# PiBoard1_1.net
KiCad netlist of a schematic drawn in EAGLE
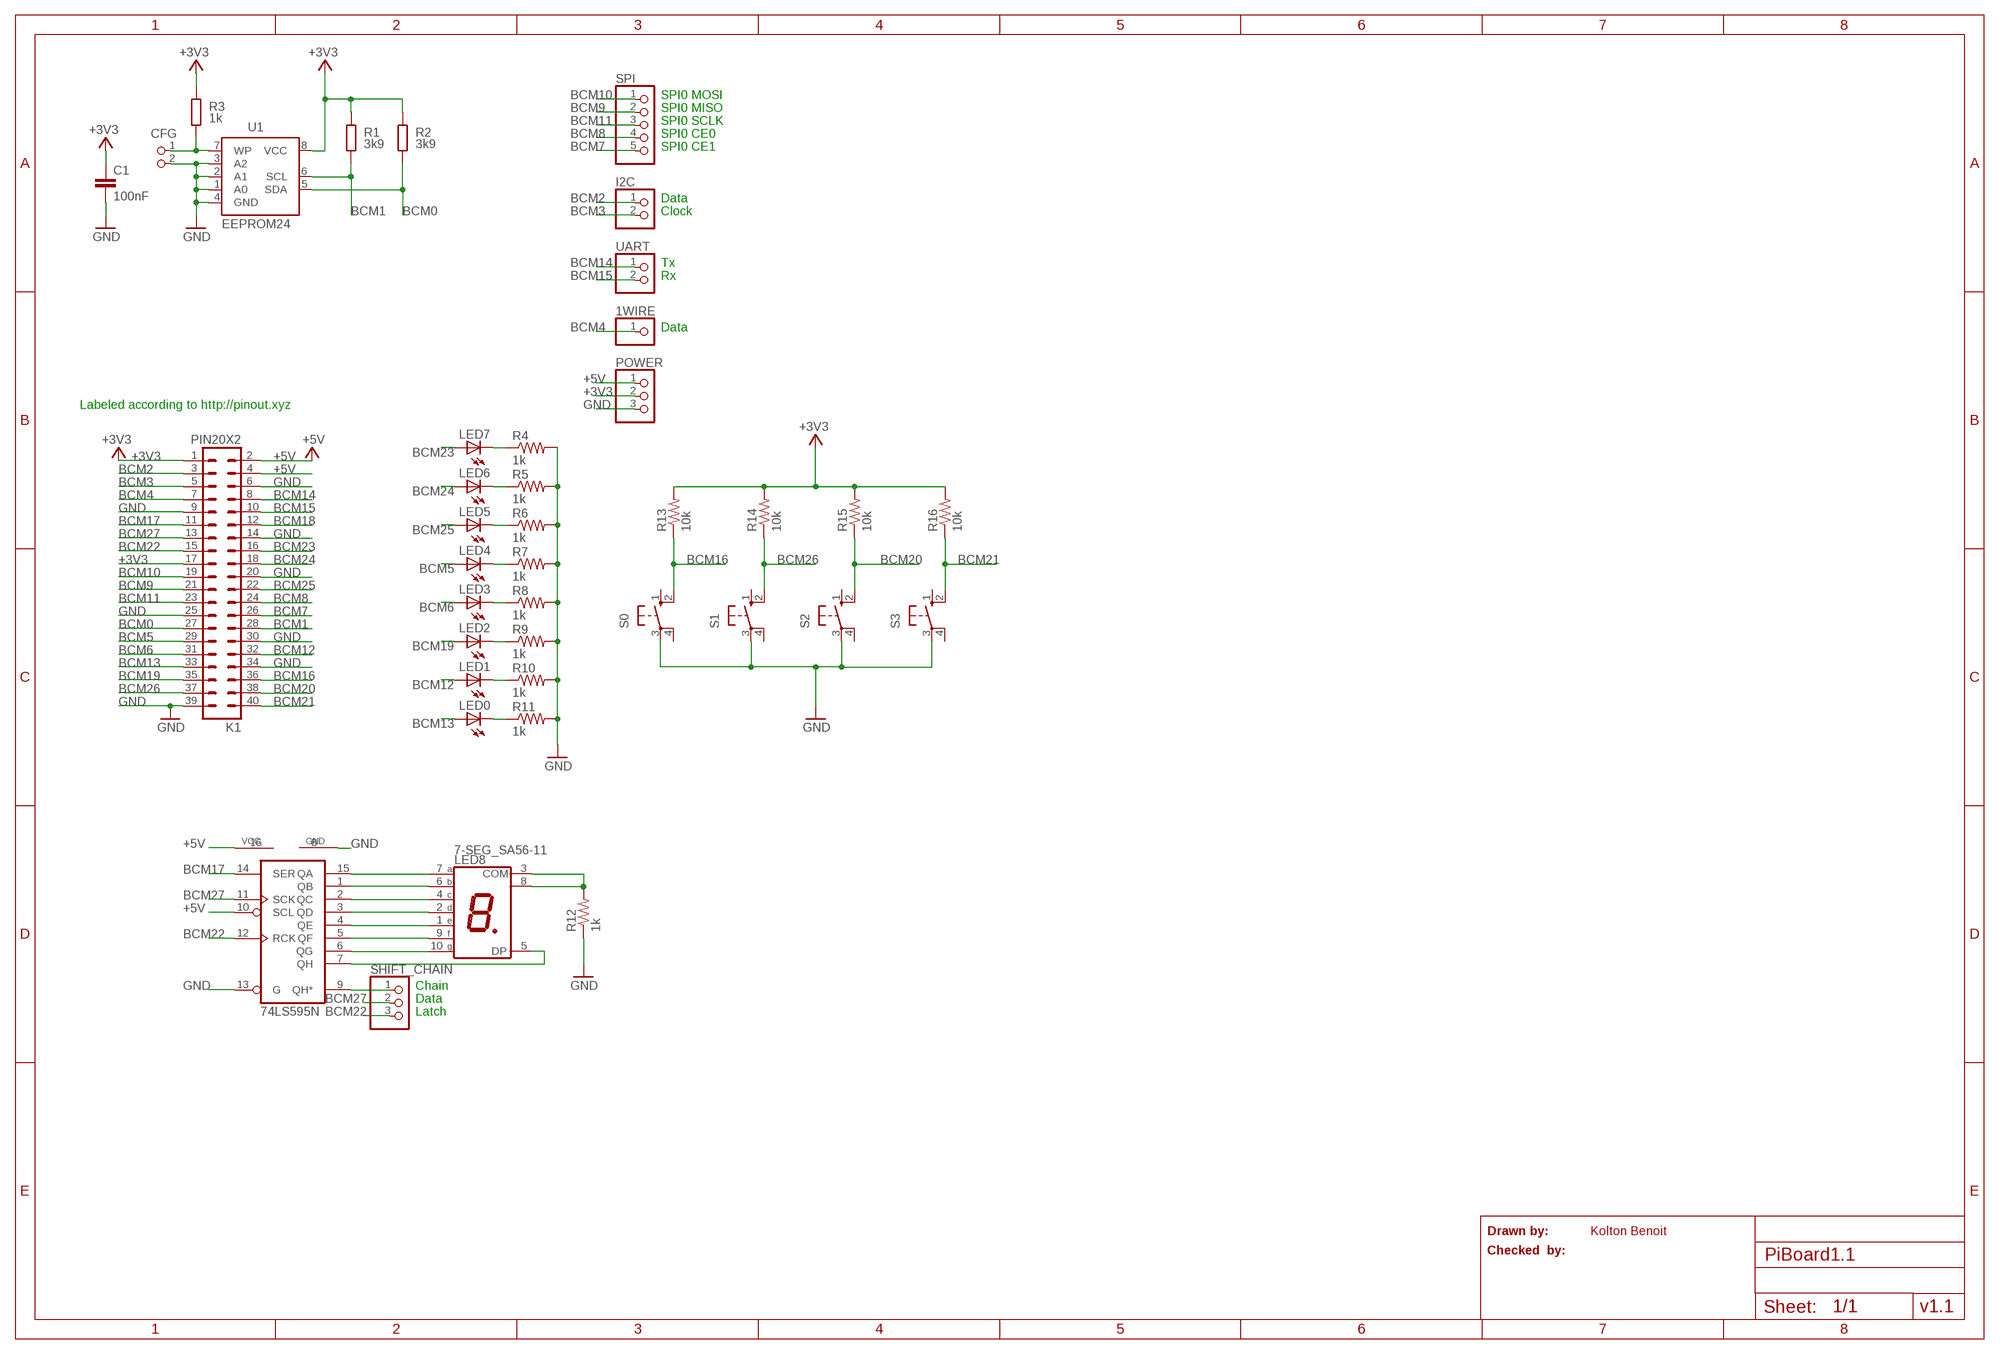
[diagram p0: schematic, sheet 1]

(export (version "E")
  (design (tool "Eeschema 10.0.6"))
  (components
    (comp (ref "1WIRE")
      (value "PINHD-1X1")
      (footprint "eagle-import:1X01")
      (libsource (lib "eagle-import") (part "PINHD-1X1"))
    )
    (comp (ref "C1")
      (value "100nF")
      (footprint "eagle-import:C0805K")
      (libsource (lib "eagle-import") (part "C-EUC0805K"))
    )
    (comp (ref "CFG")
      (value "PIN2_100")
      (footprint "eagle-import:PIN_W_2")
      (libsource (lib "eagle-import") (part "PIN2_100"))
    )
    (comp (ref "I2C")
      (value "PINHD-1X2")
      (footprint "eagle-import:1X02")
      (libsource (lib "eagle-import") (part "PINHD-1X2"))
    )
    (comp (ref "K1")
      (value "PIN20X2")
      (footprint "eagle-import:PIN_20X2")
      (libsource (lib "eagle-import") (part "PIN20X2"))
    )
    (comp (ref "LED0")
      (value "LED3MM")
      (footprint "eagle-import:LED3MM")
      (libsource (lib "eagle-import") (part "LED3MM"))
    )
    (comp (ref "LED1")
      (value "LED3MM")
      (footprint "eagle-import:LED3MM")
      (libsource (lib "eagle-import") (part "LED3MM"))
    )
    (comp (ref "LED2")
      (value "LED3MM")
      (footprint "eagle-import:LED3MM")
      (libsource (lib "eagle-import") (part "LED3MM"))
    )
    (comp (ref "LED3")
      (value "LED3MM")
      (footprint "eagle-import:LED3MM")
      (libsource (lib "eagle-import") (part "LED3MM"))
    )
    (comp (ref "LED4")
      (value "LED3MM")
      (footprint "eagle-import:LED3MM")
      (libsource (lib "eagle-import") (part "LED3MM"))
    )
    (comp (ref "LED5")
      (value "LED3MM")
      (footprint "eagle-import:LED3MM")
      (libsource (lib "eagle-import") (part "LED3MM"))
    )
    (comp (ref "LED6")
      (value "LED3MM")
      (footprint "eagle-import:LED3MM")
      (libsource (lib "eagle-import") (part "LED3MM"))
    )
    (comp (ref "LED7")
      (value "LED3MM")
      (footprint "eagle-import:LED3MM")
      (libsource (lib "eagle-import") (part "LED3MM"))
    )
    (comp (ref "LED8")
      (value "7-SEG_SA56-11")
      (footprint "eagle-import:SA56-11")
      (libsource (lib "eagle-import") (part "7-SEG_SA56-11"))
    )
    (comp (ref "POWER")
      (value "PINHD-1X3")
      (footprint "eagle-import:1X03")
      (libsource (lib "eagle-import") (part "PINHD-1X3"))
    )
    (comp (ref "R1")
      (value "3k9")
      (footprint "eagle-import:M0805@1")
      (fields (field (name "TOLERANCE") "5%"))
      (libsource (lib "eagle-import") (part "R-EU_M0805"))
    )
    (comp (ref "R2")
      (value "3k9")
      (footprint "eagle-import:M0805@1")
      (fields (field (name "TOLERANCE") "5%"))
      (libsource (lib "eagle-import") (part "R-EU_M0805"))
    )
    (comp (ref "R3")
      (value "1k")
      (footprint "eagle-import:M0805@1")
      (fields (field (name "TOLERANCE") "5%"))
      (libsource (lib "eagle-import") (part "R-EU_M0805"))
    )
    (comp (ref "R4")
      (value "1k")
      (footprint "eagle-import:0204_7")
      (libsource (lib "eagle-import") (part "R-US_0204/7"))
    )
    (comp (ref "R5")
      (value "1k")
      (footprint "eagle-import:0204_7")
      (libsource (lib "eagle-import") (part "R-US_0204/7"))
    )
    (comp (ref "R6")
      (value "1k")
      (footprint "eagle-import:0204_7")
      (libsource (lib "eagle-import") (part "R-US_0204/7"))
    )
    (comp (ref "R7")
      (value "1k")
      (footprint "eagle-import:0204_7")
      (libsource (lib "eagle-import") (part "R-US_0204/7"))
    )
    (comp (ref "R8")
      (value "1k")
      (footprint "eagle-import:0204_7")
      (libsource (lib "eagle-import") (part "R-US_0204/7"))
    )
    (comp (ref "R9")
      (value "1k")
      (footprint "eagle-import:0204_7")
      (libsource (lib "eagle-import") (part "R-US_0204/7"))
    )
    (comp (ref "R10")
      (value "1k")
      (footprint "eagle-import:0204_7")
      (libsource (lib "eagle-import") (part "R-US_0204/7"))
    )
    (comp (ref "R11")
      (value "1k")
      (footprint "eagle-import:0204_7")
      (libsource (lib "eagle-import") (part "R-US_0204/7"))
    )
    (comp (ref "R12")
      (value "1k")
      (footprint "eagle-import:0204_7")
      (libsource (lib "eagle-import") (part "R-US_0204/7"))
    )
    (comp (ref "R13")
      (value "10k")
      (footprint "eagle-import:0204_7")
      (libsource (lib "eagle-import") (part "R-US_0204/7"))
    )
    (comp (ref "R14")
      (value "10k")
      (footprint "eagle-import:0204_7")
      (libsource (lib "eagle-import") (part "R-US_0204/7"))
    )
    (comp (ref "R15")
      (value "10k")
      (footprint "eagle-import:0204_7")
      (libsource (lib "eagle-import") (part "R-US_0204/7"))
    )
    (comp (ref "R16")
      (value "10k")
      (footprint "eagle-import:0204_7")
      (libsource (lib "eagle-import") (part "R-US_0204/7"))
    )
    (comp (ref "S0")
      (value "10-XX")
      (footprint "eagle-import:B3F-10XX")
      (fields (field (name "MPN") "B3F-1000"))
      (libsource (lib "eagle-import") (part "10-XX"))
    )
    (comp (ref "S1")
      (value "10-XX")
      (footprint "eagle-import:B3F-10XX")
      (fields (field (name "MPN") "B3F-1000"))
      (libsource (lib "eagle-import") (part "10-XX"))
    )
    (comp (ref "S2")
      (value "10-XX")
      (footprint "eagle-import:B3F-10XX")
      (fields (field (name "MPN") "B3F-1000"))
      (libsource (lib "eagle-import") (part "10-XX"))
    )
    (comp (ref "S3")
      (value "10-XX")
      (footprint "eagle-import:B3F-10XX")
      (fields (field (name "MPN") "B3F-1000"))
      (libsource (lib "eagle-import") (part "10-XX"))
    )
    (comp (ref "SHIFT")
      (value "74LS595N")
      (footprint "eagle-import:DIL16")
      (libsource (lib "eagle-import") (part "74595NLS"))
    )
    (comp (ref "SHIFT_CHAIN")
      (value "PINHD-1X3")
      (footprint "eagle-import:1X03")
      (libsource (lib "eagle-import") (part "PINHD-1X3"))
    )
    (comp (ref "SPI")
      (value "PINHD-1X5")
      (footprint "eagle-import:1X05")
      (libsource (lib "eagle-import") (part "PINHD-1X5"))
    )
    (comp (ref "U1")
      (value "EEPROM24")
      (footprint "eagle-import:SOIC8")
      (libsource (lib "eagle-import") (part "EEPROM24"))
    )
    (comp (ref "UART")
      (value "PINHD-1X2")
      (footprint "eagle-import:1X02")
      (libsource (lib "eagle-import") (part "PINHD-1X2"))
    )
  )
  (nets
    (net (code "1") (name "+3V3") (class "Default")
      (node (ref "C1") (pin "1") (pinfunction "1_1") (pintype "passive"))
      (node (ref "K1") (pin "1") (pinfunction "1_1") (pintype "passive"))
      (node (ref "K1") (pin "17") (pinfunction "17_17") (pintype "passive"))
      (node (ref "POWER") (pin "2") (pinfunction "2_2") (pintype "passive"))
      (node (ref "R1") (pin "2") (pinfunction "2_2") (pintype "passive"))
      (node (ref "R13") (pin "2") (pinfunction "2_2") (pintype "passive"))
      (node (ref "R14") (pin "2") (pinfunction "2_2") (pintype "passive"))
      (node (ref "R15") (pin "2") (pinfunction "2_2") (pintype "passive"))
      (node (ref "R16") (pin "2") (pinfunction "2_2") (pintype "passive"))
      (node (ref "R2") (pin "2") (pinfunction "2_2") (pintype "passive"))
      (node (ref "R3") (pin "2") (pinfunction "2_2") (pintype "passive"))
      (node (ref "U1") (pin "8") (pinfunction "VCC_8") (pintype "power_in"))
    )
    (net (code "2") (name "+5V") (class "Default")
      (node (ref "K1") (pin "2") (pinfunction "2_2") (pintype "passive"))
      (node (ref "K1") (pin "4") (pinfunction "4_4") (pintype "passive"))
      (node (ref "POWER") (pin "1") (pinfunction "1_1") (pintype "passive"))
      (node (ref "SHIFT") (pin "10") (pinfunction "SCL_10") (pintype "input"))
      (node (ref "SHIFT") (pin "16") (pinfunction "VCC_16") (pintype "power_in"))
    )
    (net (code "3") (name "/BCM0") (class "Default")
      (node (ref "K1") (pin "27") (pinfunction "27_27") (pintype "passive"))
      (node (ref "R2") (pin "1") (pinfunction "1_1") (pintype "passive"))
      (node (ref "U1") (pin "5") (pinfunction "SDA_5") (pintype "bidirectional"))
    )
    (net (code "4") (name "/BCM1") (class "Default")
      (node (ref "K1") (pin "28") (pinfunction "28_28") (pintype "passive"))
      (node (ref "R1") (pin "1") (pinfunction "1_1") (pintype "passive"))
      (node (ref "U1") (pin "6") (pinfunction "SCL_6") (pintype "input"))
    )
    (net (code "5") (name "/BCM2") (class "Default")
      (node (ref "I2C") (pin "1") (pinfunction "1_1") (pintype "passive"))
      (node (ref "K1") (pin "3") (pinfunction "3_3") (pintype "passive"))
    )
    (net (code "6") (name "/BCM3") (class "Default")
      (node (ref "I2C") (pin "2") (pinfunction "2_2") (pintype "passive"))
      (node (ref "K1") (pin "5") (pinfunction "5_5") (pintype "passive"))
    )
    (net (code "7") (name "/BCM4") (class "Default")
      (node (ref "1WIRE") (pin "1") (pinfunction "1_1") (pintype "passive"))
      (node (ref "K1") (pin "7") (pinfunction "7_7") (pintype "passive"))
    )
    (net (code "8") (name "/BCM5") (class "Default")
      (node (ref "K1") (pin "29") (pinfunction "29_29") (pintype "passive"))
      (node (ref "LED4") (pin "A") (pinfunction "A_A") (pintype "passive"))
    )
    (net (code "9") (name "/BCM6") (class "Default")
      (node (ref "K1") (pin "31") (pinfunction "31_31") (pintype "passive"))
      (node (ref "LED3") (pin "A") (pinfunction "A_A") (pintype "passive"))
    )
    (net (code "10") (name "/BCM7") (class "Default")
      (node (ref "K1") (pin "26") (pinfunction "26_26") (pintype "passive"))
      (node (ref "SPI") (pin "5") (pinfunction "5_5") (pintype "passive"))
    )
    (net (code "11") (name "/BCM8") (class "Default")
      (node (ref "K1") (pin "24") (pinfunction "24_24") (pintype "passive"))
      (node (ref "SPI") (pin "4") (pinfunction "4_4") (pintype "passive"))
    )
    (net (code "12") (name "/BCM9") (class "Default")
      (node (ref "K1") (pin "21") (pinfunction "21_21") (pintype "passive"))
      (node (ref "SPI") (pin "2") (pinfunction "2_2") (pintype "passive"))
    )
    (net (code "13") (name "/BCM10") (class "Default")
      (node (ref "K1") (pin "19") (pinfunction "19_19") (pintype "passive"))
      (node (ref "SPI") (pin "1") (pinfunction "1_1") (pintype "passive"))
    )
    (net (code "14") (name "/BCM11") (class "Default")
      (node (ref "K1") (pin "23") (pinfunction "23_23") (pintype "passive"))
      (node (ref "SPI") (pin "3") (pinfunction "3_3") (pintype "passive"))
    )
    (net (code "15") (name "/BCM12") (class "Default")
      (node (ref "K1") (pin "32") (pinfunction "32_32") (pintype "passive"))
      (node (ref "LED1") (pin "A") (pinfunction "A_A") (pintype "passive"))
    )
    (net (code "16") (name "/BCM13") (class "Default")
      (node (ref "K1") (pin "33") (pinfunction "33_33") (pintype "passive"))
      (node (ref "LED0") (pin "A") (pinfunction "A_A") (pintype "passive"))
    )
    (net (code "17") (name "/BCM14") (class "Default")
      (node (ref "K1") (pin "8") (pinfunction "8_8") (pintype "passive"))
      (node (ref "UART") (pin "1") (pinfunction "1_1") (pintype "passive"))
    )
    (net (code "18") (name "/BCM15") (class "Default")
      (node (ref "K1") (pin "10") (pinfunction "10_10") (pintype "passive"))
      (node (ref "UART") (pin "2") (pinfunction "2_2") (pintype "passive"))
    )
    (net (code "19") (name "/BCM16") (class "Default")
      (node (ref "K1") (pin "36") (pinfunction "36_36") (pintype "passive"))
      (node (ref "R13") (pin "1") (pinfunction "1_1") (pintype "passive"))
      (node (ref "S0") (pin "2") (pinfunction "S1_2") (pintype "passive"))
    )
    (net (code "20") (name "/BCM17") (class "Default")
      (node (ref "K1") (pin "11") (pinfunction "11_11") (pintype "passive"))
      (node (ref "SHIFT") (pin "14") (pinfunction "SER_14") (pintype "input"))
    )
    (net (code "21") (name "/BCM18") (class "Default")
      (node (ref "K1") (pin "12") (pinfunction "12_12") (pintype "passive"))
    )
    (net (code "22") (name "/BCM19") (class "Default")
      (node (ref "K1") (pin "35") (pinfunction "35_35") (pintype "passive"))
      (node (ref "LED2") (pin "A") (pinfunction "A_A") (pintype "passive"))
    )
    (net (code "23") (name "/BCM20") (class "Default")
      (node (ref "K1") (pin "38") (pinfunction "38_38") (pintype "passive"))
      (node (ref "R15") (pin "1") (pinfunction "1_1") (pintype "passive"))
      (node (ref "S2") (pin "2") (pinfunction "S1_2") (pintype "passive"))
    )
    (net (code "24") (name "/BCM21") (class "Default")
      (node (ref "K1") (pin "40") (pinfunction "40_40") (pintype "passive"))
      (node (ref "R16") (pin "1") (pinfunction "1_1") (pintype "passive"))
      (node (ref "S3") (pin "2") (pinfunction "S1_2") (pintype "passive"))
    )
    (net (code "25") (name "/BCM22") (class "Default")
      (node (ref "K1") (pin "15") (pinfunction "15_15") (pintype "passive"))
      (node (ref "SHIFT") (pin "12") (pinfunction "RCK_12") (pintype "input"))
      (node (ref "SHIFT_CHAIN") (pin "3") (pinfunction "3_3") (pintype "passive"))
    )
    (net (code "26") (name "/BCM23") (class "Default")
      (node (ref "K1") (pin "16") (pinfunction "16_16") (pintype "passive"))
      (node (ref "LED7") (pin "A") (pinfunction "A_A") (pintype "passive"))
    )
    (net (code "27") (name "/BCM24") (class "Default")
      (node (ref "K1") (pin "18") (pinfunction "18_18") (pintype "passive"))
      (node (ref "LED6") (pin "A") (pinfunction "A_A") (pintype "passive"))
    )
    (net (code "28") (name "/BCM25") (class "Default")
      (node (ref "K1") (pin "22") (pinfunction "22_22") (pintype "passive"))
      (node (ref "LED5") (pin "A") (pinfunction "A_A") (pintype "passive"))
    )
    (net (code "29") (name "/BCM26") (class "Default")
      (node (ref "K1") (pin "37") (pinfunction "37_37") (pintype "passive"))
      (node (ref "R14") (pin "1") (pinfunction "1_1") (pintype "passive"))
      (node (ref "S1") (pin "2") (pinfunction "S1_2") (pintype "passive"))
    )
    (net (code "30") (name "/BCM27") (class "Default")
      (node (ref "K1") (pin "13") (pinfunction "13_13") (pintype "passive"))
      (node (ref "SHIFT") (pin "11") (pinfunction "SCK_11") (pintype "input"))
      (node (ref "SHIFT_CHAIN") (pin "2") (pinfunction "2_2") (pintype "passive"))
    )
    (net (code "31") (name "GND") (class "Default")
      (node (ref "C1") (pin "2") (pinfunction "2_2") (pintype "passive"))
      (node (ref "CFG") (pin "2") (pinfunction "2_2") (pintype "passive"))
      (node (ref "K1") (pin "14") (pinfunction "14_14") (pintype "passive"))
      (node (ref "K1") (pin "20") (pinfunction "20_20") (pintype "passive"))
      (node (ref "K1") (pin "25") (pinfunction "25_25") (pintype "passive"))
      (node (ref "K1") (pin "30") (pinfunction "30_30") (pintype "passive"))
      (node (ref "K1") (pin "34") (pinfunction "34_34") (pintype "passive"))
      (node (ref "K1") (pin "39") (pinfunction "39_39") (pintype "passive"))
      (node (ref "K1") (pin "6") (pinfunction "6_6") (pintype "passive"))
      (node (ref "K1") (pin "9") (pinfunction "9_9") (pintype "passive"))
      (node (ref "POWER") (pin "3") (pinfunction "3_3") (pintype "passive"))
      (node (ref "R10") (pin "2") (pinfunction "2_2") (pintype "passive"))
      (node (ref "R11") (pin "2") (pinfunction "2_2") (pintype "passive"))
      (node (ref "R12") (pin "1") (pinfunction "1_1") (pintype "passive"))
      (node (ref "R4") (pin "2") (pinfunction "2_2") (pintype "passive"))
      (node (ref "R5") (pin "2") (pinfunction "2_2") (pintype "passive"))
      (node (ref "R6") (pin "2") (pinfunction "2_2") (pintype "passive"))
      (node (ref "R7") (pin "2") (pinfunction "2_2") (pintype "passive"))
      (node (ref "R8") (pin "2") (pinfunction "2_2") (pintype "passive"))
      (node (ref "R9") (pin "2") (pinfunction "2_2") (pintype "passive"))
      (node (ref "S0") (pin "3") (pinfunction "P_3") (pintype "passive"))
      (node (ref "S1") (pin "3") (pinfunction "P_3") (pintype "passive"))
      (node (ref "S2") (pin "3") (pinfunction "P_3") (pintype "passive"))
      (node (ref "S3") (pin "3") (pinfunction "P_3") (pintype "passive"))
      (node (ref "SHIFT") (pin "13") (pinfunction "G_13") (pintype "input"))
      (node (ref "SHIFT") (pin "8") (pinfunction "GND_8") (pintype "power_in"))
      (node (ref "U1") (pin "1") (pinfunction "A0_1") (pintype "input"))
      (node (ref "U1") (pin "2") (pinfunction "A1_2") (pintype "input"))
      (node (ref "U1") (pin "3") (pinfunction "A2_3") (pintype "input"))
      (node (ref "U1") (pin "4") (pinfunction "GND_4") (pintype "power_in"))
    )
    (net (code "32") (name "Net-(LED0-C)") (class "Default")
      (node (ref "LED0") (pin "K") (pinfunction "C_K") (pintype "passive"))
      (node (ref "R11") (pin "1") (pinfunction "1_1") (pintype "passive"))
    )
    (net (code "33") (name "Net-(LED1-C)") (class "Default")
      (node (ref "LED1") (pin "K") (pinfunction "C_K") (pintype "passive"))
      (node (ref "R10") (pin "1") (pinfunction "1_1") (pintype "passive"))
    )
    (net (code "34") (name "Net-(LED2-C)") (class "Default")
      (node (ref "LED2") (pin "K") (pinfunction "C_K") (pintype "passive"))
      (node (ref "R9") (pin "1") (pinfunction "1_1") (pintype "passive"))
    )
    (net (code "35") (name "Net-(LED3-C)") (class "Default")
      (node (ref "LED3") (pin "K") (pinfunction "C_K") (pintype "passive"))
      (node (ref "R8") (pin "1") (pinfunction "1_1") (pintype "passive"))
    )
    (net (code "36") (name "Net-(LED4-C)") (class "Default")
      (node (ref "LED4") (pin "K") (pinfunction "C_K") (pintype "passive"))
      (node (ref "R7") (pin "1") (pinfunction "1_1") (pintype "passive"))
    )
    (net (code "37") (name "Net-(LED5-C)") (class "Default")
      (node (ref "LED5") (pin "K") (pinfunction "C_K") (pintype "passive"))
      (node (ref "R6") (pin "1") (pinfunction "1_1") (pintype "passive"))
    )
    (net (code "38") (name "Net-(LED6-C)") (class "Default")
      (node (ref "LED6") (pin "K") (pinfunction "C_K") (pintype "passive"))
      (node (ref "R5") (pin "1") (pinfunction "1_1") (pintype "passive"))
    )
    (net (code "39") (name "Net-(LED7-C)") (class "Default")
      (node (ref "LED7") (pin "K") (pinfunction "C_K") (pintype "passive"))
      (node (ref "R4") (pin "1") (pinfunction "1_1") (pintype "passive"))
    )
    (net (code "40") (name "Net-(LED8-A)") (class "Default")
      (node (ref "LED8") (pin "7") (pinfunction "A_7") (pintype "passive"))
      (node (ref "SHIFT") (pin "15") (pinfunction "QA_15") (pintype "tri_state"))
    )
    (net (code "41") (name "Net-(LED8-B)") (class "Default")
      (node (ref "LED8") (pin "6") (pinfunction "B_6") (pintype "passive"))
      (node (ref "SHIFT") (pin "1") (pinfunction "QB_1") (pintype "tri_state"))
    )
    (net (code "42") (name "Net-(LED8-C)") (class "Default")
      (node (ref "LED8") (pin "4") (pinfunction "C_4") (pintype "passive"))
      (node (ref "SHIFT") (pin "2") (pinfunction "QC_2") (pintype "tri_state"))
    )
    (net (code "43") (name "Net-(LED8-COM-Pad3)") (class "Default")
      (node (ref "LED8") (pin "3") (pinfunction "COM_3") (pintype "passive"))
      (node (ref "LED8") (pin "8") (pinfunction "COM_8") (pintype "passive"))
      (node (ref "R12") (pin "2") (pinfunction "2_2") (pintype "passive"))
    )
    (net (code "44") (name "Net-(LED8-D)") (class "Default")
      (node (ref "LED8") (pin "2") (pinfunction "D_2") (pintype "passive"))
      (node (ref "SHIFT") (pin "3") (pinfunction "QD_3") (pintype "tri_state"))
    )
    (net (code "45") (name "Net-(LED8-DP)") (class "Default")
      (node (ref "LED8") (pin "5") (pinfunction "DP_5") (pintype "passive"))
      (node (ref "SHIFT") (pin "7") (pinfunction "QH_7") (pintype "tri_state"))
    )
    (net (code "46") (name "Net-(LED8-E)") (class "Default")
      (node (ref "LED8") (pin "1") (pinfunction "E_1") (pintype "passive"))
      (node (ref "SHIFT") (pin "4") (pinfunction "QE_4") (pintype "tri_state"))
    )
    (net (code "47") (name "Net-(LED8-F)") (class "Default")
      (node (ref "LED8") (pin "9") (pinfunction "F_9") (pintype "passive"))
      (node (ref "SHIFT") (pin "5") (pinfunction "QF_5") (pintype "tri_state"))
    )
    (net (code "48") (name "Net-(LED8-G)") (class "Default")
      (node (ref "LED8") (pin "10") (pinfunction "G_10") (pintype "passive"))
      (node (ref "SHIFT") (pin "6") (pinfunction "QG_6") (pintype "tri_state"))
    )
    (net (code "49") (name "Net-(SHIFTA-QH*)") (class "Default")
      (node (ref "SHIFT") (pin "9") (pinfunction "QH*_9") (pintype "tri_state"))
      (node (ref "SHIFT_CHAIN") (pin "1") (pinfunction "1_1") (pintype "passive"))
    )
    (net (code "50") (name "Net-(U1-WP)") (class "Default")
      (node (ref "CFG") (pin "1") (pinfunction "1_1") (pintype "passive"))
      (node (ref "R3") (pin "1") (pinfunction "1_1") (pintype "passive"))
      (node (ref "U1") (pin "7") (pinfunction "WP_7") (pintype "input"))
    )
    (net (code "51") (name "unconnected-(S0-P1-Pad4)") (class "Default")
      (node (ref "S0") (pin "4") (pinfunction "P1_4") (pintype "passive"))
    )
    (net (code "52") (name "unconnected-(S0-S-Pad1)") (class "Default")
      (node (ref "S0") (pin "1") (pinfunction "S_1") (pintype "passive"))
    )
    (net (code "53") (name "unconnected-(S1-P1-Pad4)") (class "Default")
      (node (ref "S1") (pin "4") (pinfunction "P1_4") (pintype "passive"))
    )
    (net (code "54") (name "unconnected-(S1-S-Pad1)") (class "Default")
      (node (ref "S1") (pin "1") (pinfunction "S_1") (pintype "passive"))
    )
    (net (code "55") (name "unconnected-(S2-P1-Pad4)") (class "Default")
      (node (ref "S2") (pin "4") (pinfunction "P1_4") (pintype "passive"))
    )
    (net (code "56") (name "unconnected-(S2-S-Pad1)") (class "Default")
      (node (ref "S2") (pin "1") (pinfunction "S_1") (pintype "passive"))
    )
    (net (code "57") (name "unconnected-(S3-P1-Pad4)") (class "Default")
      (node (ref "S3") (pin "4") (pinfunction "P1_4") (pintype "passive"))
    )
    (net (code "58") (name "unconnected-(S3-S-Pad1)") (class "Default")
      (node (ref "S3") (pin "1") (pinfunction "S_1") (pintype "passive"))
    )
  )
)
